# Adafruit_3_5in_480x320.net
KiCad netlist of a schematic drawn in EAGLE
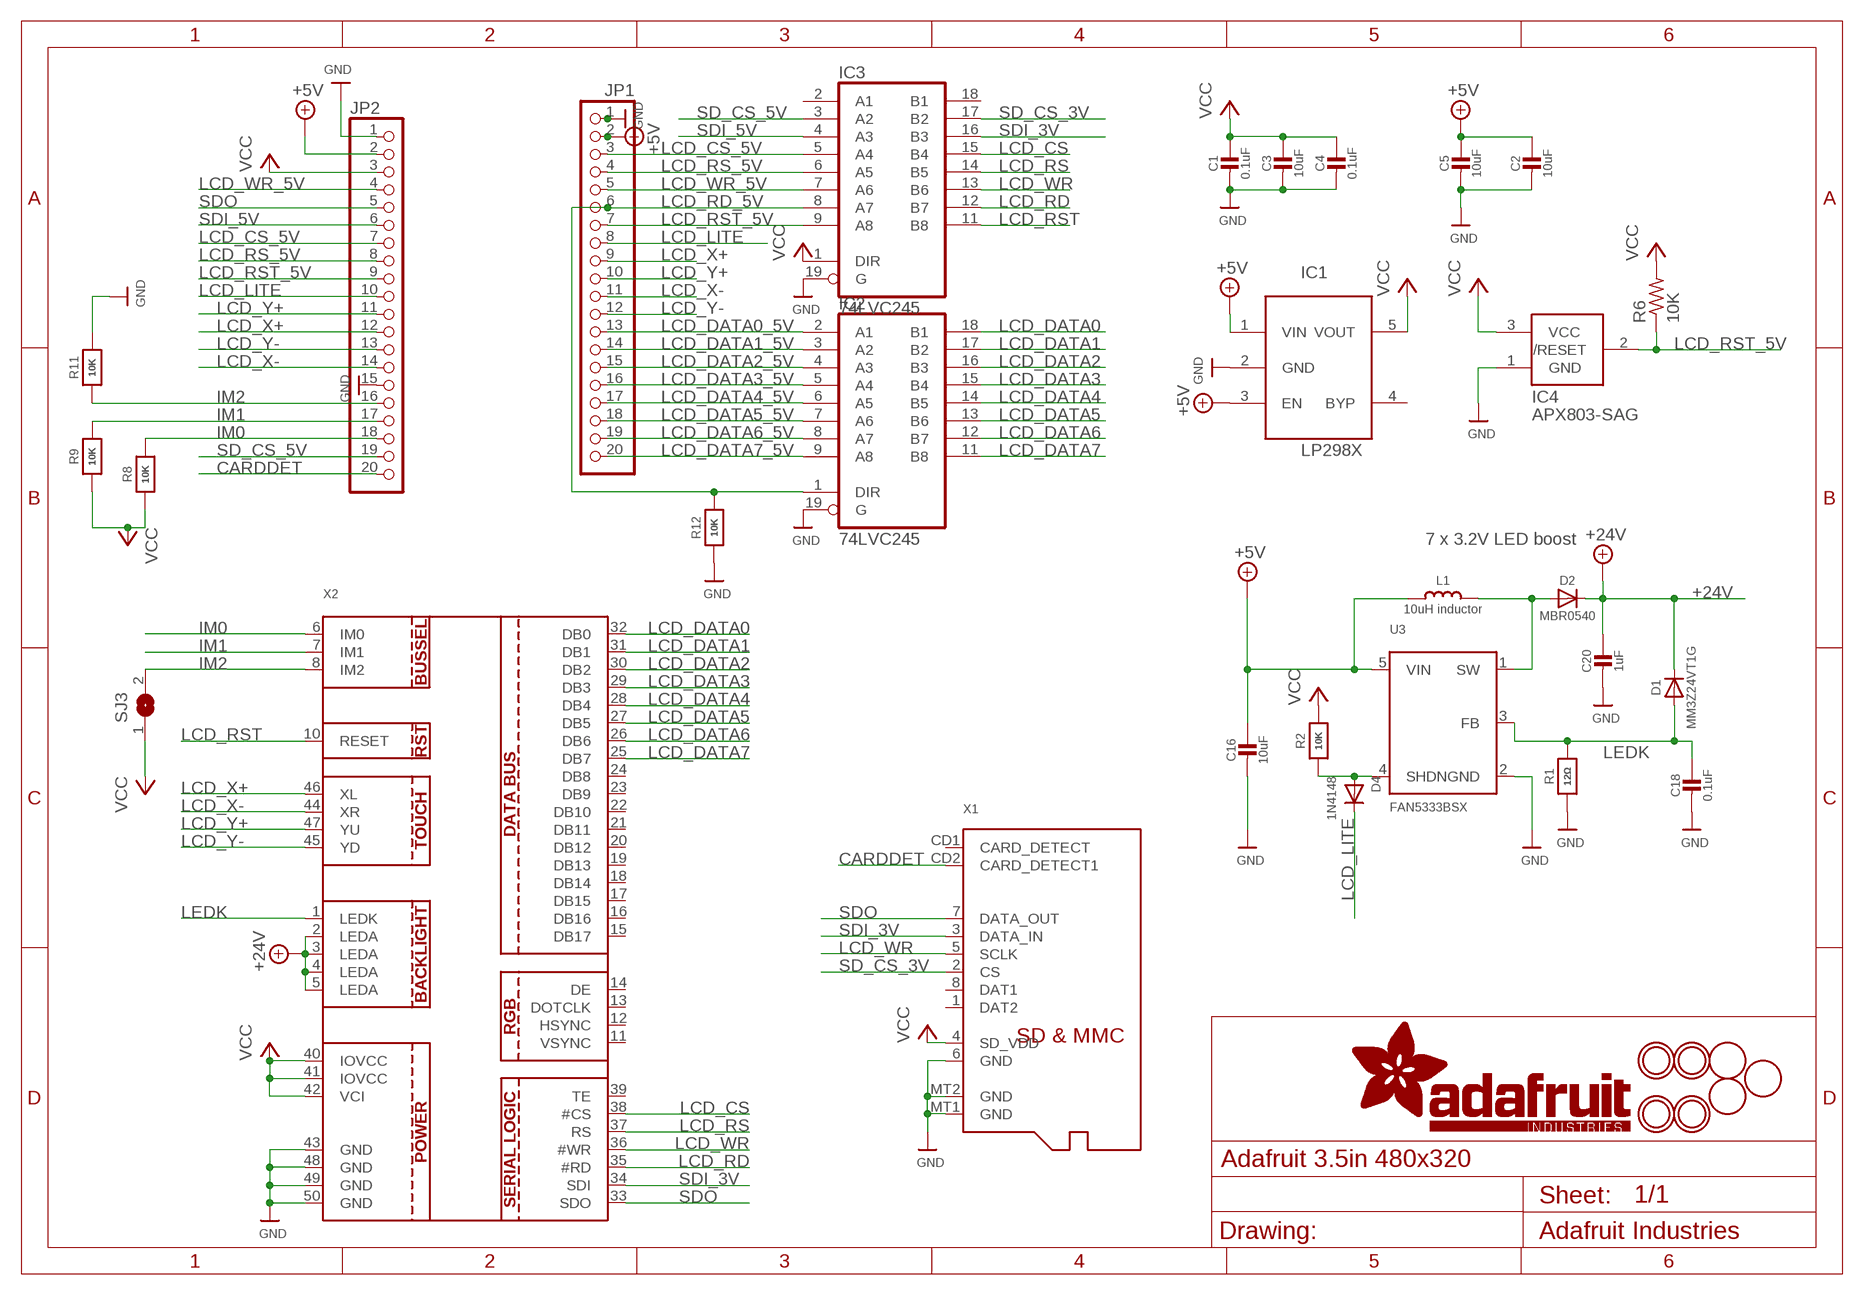
[diagram p0: schematic, sheet 1]

(export (version "E")
  (design (tool "Eeschema 10.0.6"))
  (components
    (comp (ref "C1")
      (value "0.1uF")
      (footprint "eagle-import:0805-NO")
      (libsource (lib "eagle-import") (part "CAP_CERAMIC0805-NOOUTLINE"))
    )
    (comp (ref "C2")
      (value "10uF")
      (footprint "eagle-import:0805-NO")
      (libsource (lib "eagle-import") (part "CAP_CERAMIC0805-NOOUTLINE"))
    )
    (comp (ref "C3")
      (value "10uF")
      (footprint "eagle-import:0805-NO")
      (libsource (lib "eagle-import") (part "CAP_CERAMIC0805-NOOUTLINE"))
    )
    (comp (ref "C4")
      (value "0.1uF")
      (footprint "eagle-import:0805-NO")
      (libsource (lib "eagle-import") (part "CAP_CERAMIC0805-NOOUTLINE"))
    )
    (comp (ref "C5")
      (value "10uF")
      (footprint "eagle-import:0805-NO")
      (libsource (lib "eagle-import") (part "CAP_CERAMIC0805-NOOUTLINE"))
    )
    (comp (ref "C16")
      (value "10uF")
      (footprint "eagle-import:_0805MP")
      (libsource (lib "eagle-import") (part "CAP_CERAMIC_0805MP"))
    )
    (comp (ref "C18")
      (value "0.1uF")
      (footprint "eagle-import:0805-NO")
      (libsource (lib "eagle-import") (part "CAP_CERAMIC0805-NOOUTLINE"))
    )
    (comp (ref "C20")
      (value "1uF")
      (footprint "eagle-import:0805-NO")
      (libsource (lib "eagle-import") (part "CAP_CERAMIC0805-NOOUTLINE"))
    )
    (comp (ref "D1")
      (value "MM3Z24VT1G")
      (footprint "eagle-import:SMADIODE")
      (libsource (lib "eagle-import") (part "microbuilder_DIODESMA"))
    )
    (comp (ref "D2")
      (value "MBR0540")
      (footprint "eagle-import:SOD-123")
      (libsource (lib "eagle-import") (part "microbuilder_DIODESOD-123"))
    )
    (comp (ref "D4")
      (value "1N4148")
      (footprint "eagle-import:SOD-323F")
      (libsource (lib "eagle-import") (part "DIODESOD-323F"))
    )
    (comp (ref "IC1")
      (value "MIC5225-3.3")
      (footprint "eagle-import:SOT23-5L")
      (libsource (lib "eagle-import") (part "LP298XS"))
    )
    (comp (ref "IC2")
      (value "74LVC245")
      (footprint "eagle-import:SO20W")
      (libsource (lib "eagle-import") (part "74245DWACT"))
    )
    (comp (ref "IC3")
      (value "74LVC245")
      (footprint "eagle-import:SO20W")
      (libsource (lib "eagle-import") (part "74245DWACT"))
    )
    (comp (ref "IC4")
      (value "APX803-SAG")
      (footprint "eagle-import:SOT23")
      (libsource (lib "eagle-import") (part "AXP083-SAG"))
    )
    (comp (ref "JP1")
      (value "HEADER-1X20ROUND")
      (footprint "eagle-import:1X20_ROUND")
      (libsource (lib "eagle-import") (part "HEADER-1X20ROUND"))
    )
    (comp (ref "JP2")
      (value "HEADER-1X20ROUND")
      (footprint "eagle-import:1X20_ROUND")
      (libsource (lib "eagle-import") (part "HEADER-1X20ROUND"))
    )
    (comp (ref "L1")
      (value "10uH inductor")
      (footprint "eagle-import:INDUCTOR_5X5MM_NR5040_NOTHERMALS")
      (libsource (lib "eagle-import") (part "INDUCTORNR5040"))
    )
    (comp (ref "R1")
      (value "12Ω")
      (footprint "eagle-import:_0805MP")
      (libsource (lib "eagle-import") (part "RESISTOR_0805MP"))
    )
    (comp (ref "R2")
      (value "10K")
      (footprint "eagle-import:0805-NO")
      (libsource (lib "eagle-import") (part "RESISTOR0805_NOOUTLINE"))
    )
    (comp (ref "R6")
      (value "10K")
      (footprint "eagle-import:R0805")
      (libsource (lib "eagle-import") (part "R-US_R0805"))
    )
    (comp (ref "R8")
      (value "10K")
      (footprint "eagle-import:0805-NO")
      (libsource (lib "eagle-import") (part "RESISTOR0805_NOOUTLINE"))
    )
    (comp (ref "R9")
      (value "10K")
      (footprint "eagle-import:0805-NO")
      (libsource (lib "eagle-import") (part "RESISTOR0805_NOOUTLINE"))
    )
    (comp (ref "R11")
      (value "10K")
      (footprint "eagle-import:0805-NO")
      (libsource (lib "eagle-import") (part "RESISTOR0805_NOOUTLINE"))
    )
    (comp (ref "R12")
      (value "10K")
      (footprint "eagle-import:0805-NO")
      (libsource (lib "eagle-import") (part "RESISTOR0805_NOOUTLINE"))
    )
    (comp (ref "SJ3")
      (value "SOLDERJUMPER")
      (footprint "eagle-import:SOLDERJUMPER_ARROW_NOPASTE")
      (libsource (lib "eagle-import") (part "SOLDERJUMPER"))
    )
    (comp (ref "U$7")
      (value "MOUNTINGHOLE3.0THIN")
      (footprint "eagle-import:MOUNTINGHOLE_3.0_PLATEDTHIN")
      (libsource (lib "eagle-import") (part "MOUNTINGHOLE3.0THIN"))
    )
    (comp (ref "U$9")
      (value "FIDUCIAL")
      (footprint "eagle-import:FIDUCIAL_1MM")
      (libsource (lib "eagle-import") (part "FIDUCIAL"))
    )
    (comp (ref "U$11")
      (value "FIDUCIAL")
      (footprint "eagle-import:FIDUCIAL_1MM")
      (libsource (lib "eagle-import") (part "FIDUCIAL"))
    )
    (comp (ref "U$15")
      (value "MOUNTINGHOLE3.0THIN")
      (footprint "eagle-import:MOUNTINGHOLE_3.0_PLATEDTHIN")
      (libsource (lib "eagle-import") (part "MOUNTINGHOLE3.0THIN"))
    )
    (comp (ref "U$16")
      (value "MOUNTINGHOLE3.0THIN")
      (footprint "eagle-import:MOUNTINGHOLE_3.0_PLATEDTHIN")
      (libsource (lib "eagle-import") (part "MOUNTINGHOLE3.0THIN"))
    )
    (comp (ref "U$17")
      (value "MOUNTINGHOLE3.0THIN")
      (footprint "eagle-import:MOUNTINGHOLE_3.0_PLATEDTHIN")
      (libsource (lib "eagle-import") (part "MOUNTINGHOLE3.0THIN"))
    )
    (comp (ref "U$23")
      (value "FIDUCIAL")
      (footprint "eagle-import:FIDUCIAL_1MM")
      (libsource (lib "eagle-import") (part "FIDUCIAL"))
    )
    (comp (ref "U3")
      (value "FAN5333BSX")
      (footprint "eagle-import:SOT23-5@1")
      (libsource (lib "eagle-import") (part "FAN5331"))
    )
    (comp (ref "X1")
      (value "MICROSD")
      (footprint "eagle-import:MICROSD")
      (libsource (lib "eagle-import") (part "MICROSD"))
    )
    (comp (ref "X2")
      (value "DISP_LCD_3.5IN_320X480_50PIN")
      (footprint "eagle-import:TFT_3.5IN_320X480_50PIN")
      (libsource (lib "eagle-import") (part "DISP_LCD_3.5IN_320X480_50PIN"))
    )
  )
  (nets
    (net (code "1") (name "+5V") (class "Default")
      (node (ref "C16") (pin "1") (pinfunction "1_1") (pintype "passive"))
      (node (ref "C2") (pin "1") (pinfunction "1_1") (pintype "passive"))
      (node (ref "C5") (pin "1") (pinfunction "1_1") (pintype "passive"))
      (node (ref "IC1") (pin "1") (pinfunction "VIN_1") (pintype "bidirectional"))
      (node (ref "IC1") (pin "3") (pinfunction "EN_3") (pintype "bidirectional"))
      (node (ref "JP1") (pin "2") (pinfunction "2_2") (pintype "passive"))
      (node (ref "JP2") (pin "2") (pinfunction "2_2") (pintype "passive"))
      (node (ref "L1") (pin "P$1") (pinfunction "1_P$1") (pintype "passive"))
      (node (ref "U3") (pin "5") (pinfunction "VIN_5") (pintype "bidirectional"))
    )
    (net (code "2") (name "+24V") (class "Default")
      (node (ref "C20") (pin "1") (pinfunction "1_1") (pintype "passive"))
      (node (ref "D1") (pin "C") (pinfunction "C_C") (pintype "passive"))
      (node (ref "D2") (pin "C") (pinfunction "C_C") (pintype "passive"))
      (node (ref "X2") (pin "2") (pinfunction "LEDA_2") (pintype "bidirectional"))
      (node (ref "X2") (pin "3") (pinfunction "LEDA_3") (pintype "bidirectional"))
      (node (ref "X2") (pin "4") (pinfunction "LEDA_4") (pintype "bidirectional"))
      (node (ref "X2") (pin "5") (pinfunction "LEDA_5") (pintype "bidirectional"))
    )
    (net (code "3") (name "/CARDDET") (class "Default")
      (node (ref "JP2") (pin "20") (pinfunction "20_20") (pintype "passive"))
      (node (ref "X1") (pin "CD2") (pinfunction "CARD_DETECT1_CD2") (pintype "passive"))
    )
    (net (code "4") (name "/IM0") (class "Default")
      (node (ref "JP2") (pin "18") (pinfunction "18_18") (pintype "passive"))
      (node (ref "R8") (pin "2") (pinfunction "2_2") (pintype "passive"))
      (node (ref "X2") (pin "6") (pinfunction "IM0_6") (pintype "bidirectional"))
    )
    (net (code "5") (name "/IM1") (class "Default")
      (node (ref "JP2") (pin "17") (pinfunction "17_17") (pintype "passive"))
      (node (ref "R9") (pin "2") (pinfunction "2_2") (pintype "passive"))
      (node (ref "X2") (pin "7") (pinfunction "IM1_7") (pintype "bidirectional"))
    )
    (net (code "6") (name "/IM2") (class "Default")
      (node (ref "JP2") (pin "16") (pinfunction "16_16") (pintype "passive"))
      (node (ref "R11") (pin "1") (pinfunction "1_1") (pintype "passive"))
      (node (ref "SJ3") (pin "2") (pinfunction "2_2") (pintype "passive"))
      (node (ref "X2") (pin "8") (pinfunction "IM2_8") (pintype "bidirectional"))
    )
    (net (code "7") (name "/LCD_CS") (class "Default")
      (node (ref "IC3") (pin "15") (pinfunction "B4_15") (pintype "bidirectional"))
      (node (ref "X2") (pin "38") (pinfunction "#CS_38") (pintype "bidirectional"))
    )
    (net (code "8") (name "/LCD_CS_5V") (class "Default")
      (node (ref "IC3") (pin "5") (pinfunction "A4_5") (pintype "bidirectional"))
      (node (ref "JP1") (pin "3") (pinfunction "3_3") (pintype "passive"))
      (node (ref "JP2") (pin "7") (pinfunction "7_7") (pintype "passive"))
    )
    (net (code "9") (name "/LCD_DATA0") (class "Default")
      (node (ref "IC2") (pin "18") (pinfunction "B1_18") (pintype "bidirectional"))
      (node (ref "X2") (pin "32") (pinfunction "DB0_32") (pintype "bidirectional"))
    )
    (net (code "10") (name "/LCD_DATA0_5V") (class "Default")
      (node (ref "IC2") (pin "2") (pinfunction "A1_2") (pintype "bidirectional"))
      (node (ref "JP1") (pin "13") (pinfunction "13_13") (pintype "passive"))
    )
    (net (code "11") (name "/LCD_DATA1") (class "Default")
      (node (ref "IC2") (pin "17") (pinfunction "B2_17") (pintype "bidirectional"))
      (node (ref "X2") (pin "31") (pinfunction "DB1_31") (pintype "bidirectional"))
    )
    (net (code "12") (name "/LCD_DATA1_5V") (class "Default")
      (node (ref "IC2") (pin "3") (pinfunction "A2_3") (pintype "bidirectional"))
      (node (ref "JP1") (pin "14") (pinfunction "14_14") (pintype "passive"))
    )
    (net (code "13") (name "/LCD_DATA2") (class "Default")
      (node (ref "IC2") (pin "16") (pinfunction "B3_16") (pintype "bidirectional"))
      (node (ref "X2") (pin "30") (pinfunction "DB2_30") (pintype "bidirectional"))
    )
    (net (code "14") (name "/LCD_DATA2_5V") (class "Default")
      (node (ref "IC2") (pin "4") (pinfunction "A3_4") (pintype "bidirectional"))
      (node (ref "JP1") (pin "15") (pinfunction "15_15") (pintype "passive"))
    )
    (net (code "15") (name "/LCD_DATA3") (class "Default")
      (node (ref "IC2") (pin "15") (pinfunction "B4_15") (pintype "bidirectional"))
      (node (ref "X2") (pin "29") (pinfunction "DB3_29") (pintype "bidirectional"))
    )
    (net (code "16") (name "/LCD_DATA3_5V") (class "Default")
      (node (ref "IC2") (pin "5") (pinfunction "A4_5") (pintype "bidirectional"))
      (node (ref "JP1") (pin "16") (pinfunction "16_16") (pintype "passive"))
    )
    (net (code "17") (name "/LCD_DATA4") (class "Default")
      (node (ref "IC2") (pin "14") (pinfunction "B5_14") (pintype "bidirectional"))
      (node (ref "X2") (pin "28") (pinfunction "DB4_28") (pintype "bidirectional"))
    )
    (net (code "18") (name "/LCD_DATA4_5V") (class "Default")
      (node (ref "IC2") (pin "6") (pinfunction "A5_6") (pintype "bidirectional"))
      (node (ref "JP1") (pin "17") (pinfunction "17_17") (pintype "passive"))
    )
    (net (code "19") (name "/LCD_DATA5") (class "Default")
      (node (ref "IC2") (pin "13") (pinfunction "B6_13") (pintype "bidirectional"))
      (node (ref "X2") (pin "27") (pinfunction "DB5_27") (pintype "bidirectional"))
    )
    (net (code "20") (name "/LCD_DATA5_5V") (class "Default")
      (node (ref "IC2") (pin "7") (pinfunction "A6_7") (pintype "bidirectional"))
      (node (ref "JP1") (pin "18") (pinfunction "18_18") (pintype "passive"))
    )
    (net (code "21") (name "/LCD_DATA6") (class "Default")
      (node (ref "IC2") (pin "12") (pinfunction "B7_12") (pintype "bidirectional"))
      (node (ref "X2") (pin "26") (pinfunction "DB6_26") (pintype "bidirectional"))
    )
    (net (code "22") (name "/LCD_DATA6_5V") (class "Default")
      (node (ref "IC2") (pin "8") (pinfunction "A7_8") (pintype "bidirectional"))
      (node (ref "JP1") (pin "19") (pinfunction "19_19") (pintype "passive"))
    )
    (net (code "23") (name "/LCD_DATA7") (class "Default")
      (node (ref "IC2") (pin "11") (pinfunction "B8_11") (pintype "bidirectional"))
      (node (ref "X2") (pin "25") (pinfunction "DB7_25") (pintype "bidirectional"))
    )
    (net (code "24") (name "/LCD_DATA7_5V") (class "Default")
      (node (ref "IC2") (pin "9") (pinfunction "A8_9") (pintype "bidirectional"))
      (node (ref "JP1") (pin "20") (pinfunction "20_20") (pintype "passive"))
    )
    (net (code "25") (name "/LCD_LITE") (class "Default")
      (node (ref "D4") (pin "C") (pinfunction "C_C") (pintype "passive"))
      (node (ref "JP1") (pin "8") (pinfunction "8_8") (pintype "passive"))
      (node (ref "JP2") (pin "10") (pinfunction "10_10") (pintype "passive"))
    )
    (net (code "26") (name "/LCD_RD") (class "Default")
      (node (ref "IC3") (pin "12") (pinfunction "B7_12") (pintype "bidirectional"))
      (node (ref "X2") (pin "35") (pinfunction "#RD_35") (pintype "bidirectional"))
    )
    (net (code "27") (name "/LCD_RD_5V") (class "Default")
      (node (ref "IC2") (pin "1") (pinfunction "DIR_1") (pintype "input"))
      (node (ref "IC3") (pin "8") (pinfunction "A7_8") (pintype "bidirectional"))
      (node (ref "JP1") (pin "6") (pinfunction "6_6") (pintype "passive"))
      (node (ref "R12") (pin "2") (pinfunction "2_2") (pintype "passive"))
    )
    (net (code "28") (name "/LCD_RS") (class "Default")
      (node (ref "IC3") (pin "14") (pinfunction "B5_14") (pintype "bidirectional"))
      (node (ref "X2") (pin "37") (pinfunction "RS_37") (pintype "bidirectional"))
    )
    (net (code "29") (name "/LCD_RST") (class "Default")
      (node (ref "IC3") (pin "11") (pinfunction "B8_11") (pintype "bidirectional"))
      (node (ref "X2") (pin "10") (pinfunction "RESET_10") (pintype "bidirectional"))
    )
    (net (code "30") (name "/LCD_RST_5V") (class "Default")
      (node (ref "IC3") (pin "9") (pinfunction "A8_9") (pintype "bidirectional"))
      (node (ref "IC4") (pin "2") (pinfunction "/RESET_2") (pintype "output"))
      (node (ref "JP1") (pin "7") (pinfunction "7_7") (pintype "passive"))
      (node (ref "JP2") (pin "9") (pinfunction "9_9") (pintype "passive"))
      (node (ref "R6") (pin "1") (pinfunction "1_1") (pintype "passive"))
    )
    (net (code "31") (name "/LCD_RS_5V") (class "Default")
      (node (ref "IC3") (pin "6") (pinfunction "A5_6") (pintype "bidirectional"))
      (node (ref "JP1") (pin "4") (pinfunction "4_4") (pintype "passive"))
      (node (ref "JP2") (pin "8") (pinfunction "8_8") (pintype "passive"))
    )
    (net (code "32") (name "/LCD_WR") (class "Default")
      (node (ref "IC3") (pin "13") (pinfunction "B6_13") (pintype "bidirectional"))
      (node (ref "X1") (pin "5") (pinfunction "SCLK_5") (pintype "input"))
      (node (ref "X2") (pin "36") (pinfunction "#WR_36") (pintype "bidirectional"))
    )
    (net (code "33") (name "/LCD_WR_5V") (class "Default")
      (node (ref "IC3") (pin "7") (pinfunction "A6_7") (pintype "bidirectional"))
      (node (ref "JP1") (pin "5") (pinfunction "5_5") (pintype "passive"))
      (node (ref "JP2") (pin "4") (pinfunction "4_4") (pintype "passive"))
    )
    (net (code "34") (name "/LCD_X+") (class "Default")
      (node (ref "JP1") (pin "9") (pinfunction "9_9") (pintype "passive"))
      (node (ref "JP2") (pin "12") (pinfunction "12_12") (pintype "passive"))
      (node (ref "X2") (pin "46") (pinfunction "XL_46") (pintype "bidirectional"))
    )
    (net (code "35") (name "/LCD_X-") (class "Default")
      (node (ref "JP1") (pin "11") (pinfunction "11_11") (pintype "passive"))
      (node (ref "JP2") (pin "14") (pinfunction "14_14") (pintype "passive"))
      (node (ref "X2") (pin "44") (pinfunction "XR_44") (pintype "bidirectional"))
    )
    (net (code "36") (name "/LCD_Y+") (class "Default")
      (node (ref "JP1") (pin "10") (pinfunction "10_10") (pintype "passive"))
      (node (ref "JP2") (pin "11") (pinfunction "11_11") (pintype "passive"))
      (node (ref "X2") (pin "47") (pinfunction "YU_47") (pintype "bidirectional"))
    )
    (net (code "37") (name "/LCD_Y-") (class "Default")
      (node (ref "JP1") (pin "12") (pinfunction "12_12") (pintype "passive"))
      (node (ref "JP2") (pin "13") (pinfunction "13_13") (pintype "passive"))
      (node (ref "X2") (pin "45") (pinfunction "YD_45") (pintype "bidirectional"))
    )
    (net (code "38") (name "/LEDK") (class "Default")
      (node (ref "C18") (pin "1") (pinfunction "1_1") (pintype "passive"))
      (node (ref "D1") (pin "A") (pinfunction "A_A") (pintype "passive"))
      (node (ref "R1") (pin "2") (pinfunction "2_2") (pintype "passive"))
      (node (ref "U3") (pin "3") (pinfunction "FB_3") (pintype "bidirectional"))
      (node (ref "X2") (pin "1") (pinfunction "LEDK_1") (pintype "bidirectional"))
    )
    (net (code "39") (name "/SDI_3V") (class "Default")
      (node (ref "IC3") (pin "16") (pinfunction "B3_16") (pintype "bidirectional"))
      (node (ref "X1") (pin "3") (pinfunction "DATA_IN_3") (pintype "input"))
      (node (ref "X2") (pin "34") (pinfunction "SDI_34") (pintype "bidirectional"))
    )
    (net (code "40") (name "/SDI_5V") (class "Default")
      (node (ref "IC3") (pin "4") (pinfunction "A3_4") (pintype "bidirectional"))
      (node (ref "JP2") (pin "6") (pinfunction "6_6") (pintype "passive"))
    )
    (net (code "41") (name "/SDO") (class "Default")
      (node (ref "JP2") (pin "5") (pinfunction "5_5") (pintype "passive"))
      (node (ref "X1") (pin "7") (pinfunction "DATA_OUT_7") (pintype "output"))
      (node (ref "X2") (pin "33") (pinfunction "SDO_33") (pintype "bidirectional"))
    )
    (net (code "42") (name "/SD_CS_3V") (class "Default")
      (node (ref "IC3") (pin "17") (pinfunction "B2_17") (pintype "bidirectional"))
      (node (ref "X1") (pin "2") (pinfunction "CS_2") (pintype "input"))
    )
    (net (code "43") (name "/SD_CS_5V") (class "Default")
      (node (ref "IC3") (pin "3") (pinfunction "A2_3") (pintype "bidirectional"))
      (node (ref "JP2") (pin "19") (pinfunction "19_19") (pintype "passive"))
    )
    (net (code "44") (name "GND") (class "Default")
      (node (ref "C1") (pin "2") (pinfunction "2_2") (pintype "passive"))
      (node (ref "C16") (pin "2") (pinfunction "2_2") (pintype "passive"))
      (node (ref "C18") (pin "2") (pinfunction "2_2") (pintype "passive"))
      (node (ref "C2") (pin "2") (pinfunction "2_2") (pintype "passive"))
      (node (ref "C20") (pin "2") (pinfunction "2_2") (pintype "passive"))
      (node (ref "C3") (pin "2") (pinfunction "2_2") (pintype "passive"))
      (node (ref "C4") (pin "2") (pinfunction "2_2") (pintype "passive"))
      (node (ref "C5") (pin "2") (pinfunction "2_2") (pintype "passive"))
      (node (ref "IC1") (pin "2") (pinfunction "GND_2") (pintype "bidirectional"))
      (node (ref "IC2") (pin "19") (pinfunction "G_19") (pintype "input"))
      (node (ref "IC3") (pin "19") (pinfunction "G_19") (pintype "input"))
      (node (ref "IC4") (pin "1") (pinfunction "GND_1") (pintype "power_in"))
      (node (ref "JP1") (pin "1") (pinfunction "1_1") (pintype "passive"))
      (node (ref "JP2") (pin "1") (pinfunction "1_1") (pintype "passive"))
      (node (ref "JP2") (pin "15") (pinfunction "15_15") (pintype "passive"))
      (node (ref "R1") (pin "1") (pinfunction "1_1") (pintype "passive"))
      (node (ref "R11") (pin "2") (pinfunction "2_2") (pintype "passive"))
      (node (ref "R12") (pin "1") (pinfunction "1_1") (pintype "passive"))
      (node (ref "U3") (pin "2") (pinfunction "GND_2") (pintype "bidirectional"))
      (node (ref "X1") (pin "6") (pinfunction "GND_6") (pintype "power_in"))
      (node (ref "X1") (pin "MT1") (pinfunction "GND_MT1") (pintype "power_in"))
      (node (ref "X1") (pin "MT2") (pinfunction "GND_MT2") (pintype "power_in"))
      (node (ref "X2") (pin "43") (pinfunction "GND_43") (pintype "bidirectional"))
      (node (ref "X2") (pin "48") (pinfunction "GND_48") (pintype "bidirectional"))
      (node (ref "X2") (pin "49") (pinfunction "GND_49") (pintype "bidirectional"))
      (node (ref "X2") (pin "50") (pinfunction "GND_50") (pintype "bidirectional"))
    )
    (net (code "45") (name "Net-(L1-2)") (class "Default")
      (node (ref "D2") (pin "A") (pinfunction "A_A") (pintype "passive"))
      (node (ref "L1") (pin "P$2") (pinfunction "2_P$2") (pintype "passive"))
      (node (ref "U3") (pin "1") (pinfunction "SW_1") (pintype "bidirectional"))
    )
    (net (code "46") (name "Net-(U3-SHDN)") (class "Default")
      (node (ref "D4") (pin "A") (pinfunction "A_A") (pintype "passive"))
      (node (ref "R2") (pin "1") (pinfunction "1_1") (pintype "passive"))
      (node (ref "U3") (pin "4") (pinfunction "SHDN_4") (pintype "bidirectional"))
    )
    (net (code "47") (name "VCC") (class "Default")
      (node (ref "C1") (pin "1") (pinfunction "1_1") (pintype "passive"))
      (node (ref "C3") (pin "1") (pinfunction "1_1") (pintype "passive"))
      (node (ref "C4") (pin "1") (pinfunction "1_1") (pintype "passive"))
      (node (ref "IC1") (pin "5") (pinfunction "VOUT_5") (pintype "bidirectional"))
      (node (ref "IC3") (pin "1") (pinfunction "DIR_1") (pintype "input"))
      (node (ref "IC4") (pin "3") (pinfunction "VCC_3") (pintype "power_in"))
      (node (ref "JP2") (pin "3") (pinfunction "3_3") (pintype "passive"))
      (node (ref "R2") (pin "2") (pinfunction "2_2") (pintype "passive"))
      (node (ref "R6") (pin "2") (pinfunction "2_2") (pintype "passive"))
      (node (ref "R8") (pin "1") (pinfunction "1_1") (pintype "passive"))
      (node (ref "R9") (pin "1") (pinfunction "1_1") (pintype "passive"))
      (node (ref "SJ3") (pin "1") (pinfunction "1_1") (pintype "passive"))
      (node (ref "X1") (pin "4") (pinfunction "SD_VDD_4") (pintype "power_in"))
      (node (ref "X2") (pin "40") (pinfunction "IOVCC_40") (pintype "bidirectional"))
      (node (ref "X2") (pin "41") (pinfunction "IOVCC_41") (pintype "bidirectional"))
      (node (ref "X2") (pin "42") (pinfunction "VCI_42") (pintype "bidirectional"))
    )
    (net (code "48") (name "unconnected-(IC1-BYP-Pad4)") (class "Default")
      (node (ref "IC1") (pin "4") (pinfunction "BYP_4") (pintype "bidirectional"))
    )
    (net (code "49") (name "unconnected-(IC3A-A1-Pad2)") (class "Default")
      (node (ref "IC3") (pin "2") (pinfunction "A1_2") (pintype "bidirectional"))
    )
    (net (code "50") (name "unconnected-(IC3A-B1-Pad18)") (class "Default")
      (node (ref "IC3") (pin "18") (pinfunction "B1_18") (pintype "bidirectional"))
    )
    (net (code "51") (name "unconnected-(X1-CARD_DETECT-PadCD1)") (class "Default")
      (node (ref "X1") (pin "CD1") (pinfunction "CARD_DETECT_CD1") (pintype "passive"))
    )
    (net (code "52") (name "unconnected-(X1-DAT1-Pad8)") (class "Default")
      (node (ref "X1") (pin "8") (pinfunction "DAT1_8") (pintype "bidirectional"))
    )
    (net (code "53") (name "unconnected-(X1-DAT2-Pad1)") (class "Default")
      (node (ref "X1") (pin "1") (pinfunction "DAT2_1") (pintype "bidirectional"))
    )
    (net (code "54") (name "unconnected-(X2-DB8-Pad24)") (class "Default")
      (node (ref "X2") (pin "24") (pinfunction "DB8_24") (pintype "bidirectional"))
    )
    (net (code "55") (name "unconnected-(X2-DB9-Pad23)") (class "Default")
      (node (ref "X2") (pin "23") (pinfunction "DB9_23") (pintype "bidirectional"))
    )
    (net (code "56") (name "unconnected-(X2-DB10-Pad22)") (class "Default")
      (node (ref "X2") (pin "22") (pinfunction "DB10_22") (pintype "bidirectional"))
    )
    (net (code "57") (name "unconnected-(X2-DB11-Pad21)") (class "Default")
      (node (ref "X2") (pin "21") (pinfunction "DB11_21") (pintype "bidirectional"))
    )
    (net (code "58") (name "unconnected-(X2-DB12-Pad20)") (class "Default")
      (node (ref "X2") (pin "20") (pinfunction "DB12_20") (pintype "bidirectional"))
    )
    (net (code "59") (name "unconnected-(X2-DB13-Pad19)") (class "Default")
      (node (ref "X2") (pin "19") (pinfunction "DB13_19") (pintype "bidirectional"))
    )
    (net (code "60") (name "unconnected-(X2-DB14-Pad18)") (class "Default")
      (node (ref "X2") (pin "18") (pinfunction "DB14_18") (pintype "bidirectional"))
    )
    (net (code "61") (name "unconnected-(X2-DB15-Pad17)") (class "Default")
      (node (ref "X2") (pin "17") (pinfunction "DB15_17") (pintype "bidirectional"))
    )
    (net (code "62") (name "unconnected-(X2-DB16-Pad16)") (class "Default")
      (node (ref "X2") (pin "16") (pinfunction "DB16_16") (pintype "bidirectional"))
    )
    (net (code "63") (name "unconnected-(X2-DB17-Pad15)") (class "Default")
      (node (ref "X2") (pin "15") (pinfunction "DB17_15") (pintype "bidirectional"))
    )
    (net (code "64") (name "unconnected-(X2-DE-Pad14)") (class "Default")
      (node (ref "X2") (pin "14") (pinfunction "DE_14") (pintype "bidirectional"))
    )
    (net (code "65") (name "unconnected-(X2-DOTCLK-Pad13)") (class "Default")
      (node (ref "X2") (pin "13") (pinfunction "DOTCLK_13") (pintype "bidirectional"))
    )
    (net (code "66") (name "unconnected-(X2-HSYNC-Pad12)") (class "Default")
      (node (ref "X2") (pin "12") (pinfunction "HSYNC_12") (pintype "bidirectional"))
    )
    (net (code "67") (name "unconnected-(X2-TE-Pad39)") (class "Default")
      (node (ref "X2") (pin "39") (pinfunction "TE_39") (pintype "bidirectional"))
    )
    (net (code "68") (name "unconnected-(X2-VSYNC-Pad11)") (class "Default")
      (node (ref "X2") (pin "11") (pinfunction "VSYNC_11") (pintype "bidirectional"))
    )
  )
)
